# base3-5pin-interface-SDA-SCL-Switch-on-o.net
KiCad netlist of a schematic drawn in EAGLE
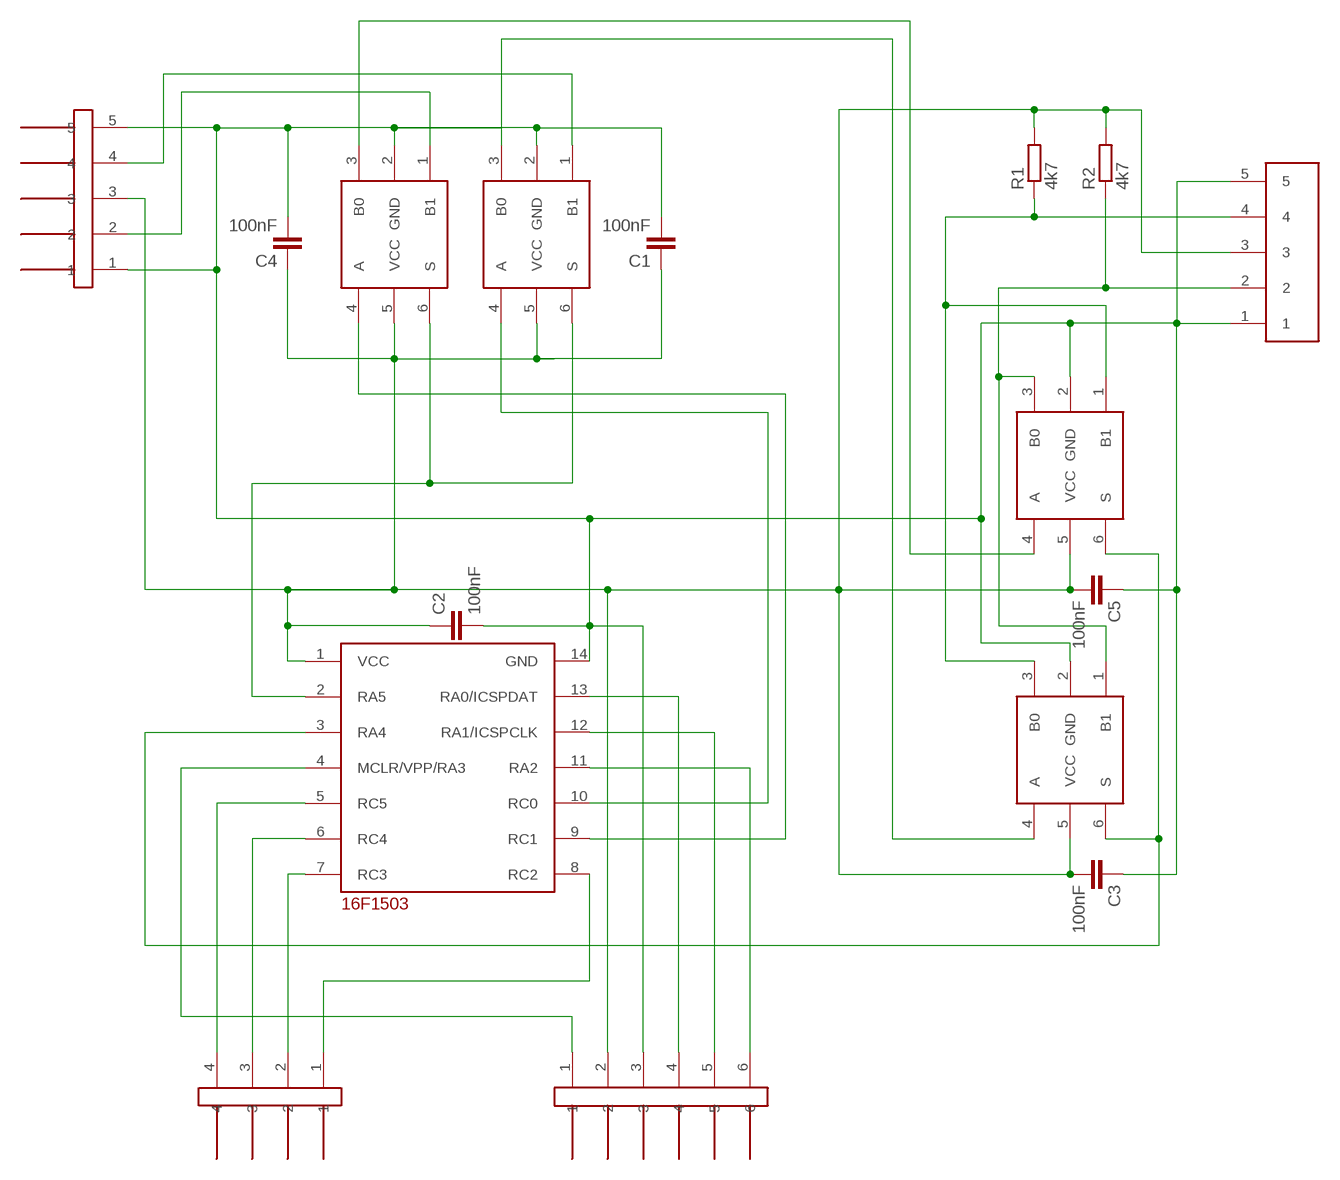
[diagram p0: schematic, sheet 1]

(export (version "E")
  (design (tool "Eeschema 10.0.6"))
  (components
    (comp (ref "C1")
      (value "100nF")
      (footprint "eagle-import:C0603")
      (libsource (lib "eagle-import") (part "C-EUC0603"))
    )
    (comp (ref "C2")
      (value "100nF")
      (footprint "eagle-import:C0603")
      (libsource (lib "eagle-import") (part "C-EUC0603"))
    )
    (comp (ref "C3")
      (value "100nF")
      (footprint "eagle-import:C0603")
      (libsource (lib "eagle-import") (part "C-EUC0603"))
    )
    (comp (ref "C4")
      (value "100nF")
      (footprint "eagle-import:C0603")
      (libsource (lib "eagle-import") (part "C-EUC0603"))
    )
    (comp (ref "C5")
      (value "100nF")
      (footprint "eagle-import:C0603")
      (libsource (lib "eagle-import") (part "C-EUC0603"))
    )
    (comp (ref "R1")
      (value "4k7")
      (footprint "eagle-import:M0805")
      (libsource (lib "eagle-import") (part "R-EU_M0805"))
    )
    (comp (ref "R2")
      (value "4k7")
      (footprint "eagle-import:M0805")
      (libsource (lib "eagle-import") (part "R-EU_M0805"))
    )
    (comp (ref "U$1")
      (value "16F103-TSSOP")
      (footprint "eagle-import:TSSOP14")
      (libsource (lib "eagle-import") (part "16F103-TSSOP"))
    )
    (comp (ref "U$2")
      (value "NC7SB3157P6X")
      (footprint "eagle-import:SC70-6L")
      (libsource (lib "eagle-import") (part "NC7SB3157P6X"))
    )
    (comp (ref "U$3")
      (value "NC7SB3157P6X")
      (footprint "eagle-import:SC70-6L")
      (libsource (lib "eagle-import") (part "NC7SB3157P6X"))
    )
    (comp (ref "U$4")
      (value "JUMPER5M-90")
      (footprint "eagle-import:JUMPER5M-90")
      (libsource (lib "eagle-import") (part "JUMPER5M-90"))
    )
    (comp (ref "U$5")
      (value "JUMPER5F-90")
      (footprint "eagle-import:JUMPER5F-90")
      (libsource (lib "eagle-import") (part "JUMPER5F-90"))
    )
    (comp (ref "U$6")
      (value "NC7SB3157P6X")
      (footprint "eagle-import:SC70-6L")
      (libsource (lib "eagle-import") (part "NC7SB3157P6X"))
    )
    (comp (ref "U$7")
      (value "NC7SB3157P6X")
      (footprint "eagle-import:SC70-6L")
      (libsource (lib "eagle-import") (part "NC7SB3157P6X"))
    )
    (comp (ref "U$8")
      (value "JUMPER6M")
      (footprint "eagle-import:JUMPER6M")
      (libsource (lib "eagle-import") (part "JUMPER6M"))
    )
    (comp (ref "U$9")
      (value "JUMPER4M")
      (footprint "eagle-import:JUMPER4M")
      (libsource (lib "eagle-import") (part "JUMPER4M"))
    )
  )
  (nets
    (net (code "1") (name "Net-(U$1-GND)") (class "Default")
      (node (ref "C1") (pin "2") (pinfunction "2_2") (pintype "passive"))
      (node (ref "C2") (pin "2") (pinfunction "2_2") (pintype "passive"))
      (node (ref "C3") (pin "1") (pinfunction "1_1") (pintype "passive"))
      (node (ref "C4") (pin "2") (pinfunction "2_2") (pintype "passive"))
      (node (ref "C5") (pin "1") (pinfunction "1_1") (pintype "passive"))
      (node (ref "U$1") (pin "14") (pinfunction "GND_14") (pintype "power_in"))
      (node (ref "U$2") (pin "2") (pinfunction "GND_2") (pintype "power_in"))
      (node (ref "U$3") (pin "2") (pinfunction "GND_2") (pintype "power_in"))
      (node (ref "U$4") (pin "1") (pinfunction "1_1") (pintype "bidirectional"))
      (node (ref "U$4") (pin "5") (pinfunction "5_5") (pintype "bidirectional"))
      (node (ref "U$5") (pin "1") (pinfunction "1_1") (pintype "bidirectional"))
      (node (ref "U$5") (pin "5") (pinfunction "5_5") (pintype "bidirectional"))
      (node (ref "U$6") (pin "2") (pinfunction "GND_2") (pintype "power_in"))
      (node (ref "U$7") (pin "2") (pinfunction "GND_2") (pintype "power_in"))
      (node (ref "U$8") (pin "3") (pinfunction "3_3") (pintype "bidirectional"))
    )
    (net (code "2") (name "Net-(U$1-MCLR{slash}VPP{slash}RA3)") (class "Default")
      (node (ref "U$1") (pin "4") (pinfunction "MCLR/VPP/RA3_4") (pintype "bidirectional"))
      (node (ref "U$8") (pin "1") (pinfunction "1_1") (pintype "bidirectional"))
    )
    (net (code "3") (name "Net-(U$1-RA0{slash}ICSPDAT)") (class "Default")
      (node (ref "U$1") (pin "13") (pinfunction "RA0/ICSPDAT_13") (pintype "bidirectional"))
      (node (ref "U$8") (pin "4") (pinfunction "4_4") (pintype "bidirectional"))
    )
    (net (code "4") (name "Net-(U$1-RA1{slash}ICSPCLK)") (class "Default")
      (node (ref "U$1") (pin "12") (pinfunction "RA1/ICSPCLK_12") (pintype "bidirectional"))
      (node (ref "U$8") (pin "5") (pinfunction "5_5") (pintype "bidirectional"))
    )
    (net (code "5") (name "Net-(U$1-RA2)") (class "Default")
      (node (ref "U$1") (pin "11") (pinfunction "RA2_11") (pintype "bidirectional"))
      (node (ref "U$8") (pin "6") (pinfunction "6_6") (pintype "bidirectional"))
    )
    (net (code "6") (name "Net-(U$1-RA4)") (class "Default")
      (node (ref "U$1") (pin "3") (pinfunction "RA4_3") (pintype "bidirectional"))
      (node (ref "U$6") (pin "6") (pinfunction "S_6") (pintype "bidirectional"))
      (node (ref "U$7") (pin "6") (pinfunction "S_6") (pintype "bidirectional"))
    )
    (net (code "7") (name "Net-(U$1-RA5)") (class "Default")
      (node (ref "U$1") (pin "2") (pinfunction "RA5_2") (pintype "bidirectional"))
      (node (ref "U$2") (pin "6") (pinfunction "S_6") (pintype "bidirectional"))
      (node (ref "U$3") (pin "6") (pinfunction "S_6") (pintype "bidirectional"))
    )
    (net (code "8") (name "Net-(U$1-RC0)") (class "Default")
      (node (ref "U$1") (pin "10") (pinfunction "RC0_10") (pintype "bidirectional"))
      (node (ref "U$2") (pin "4") (pinfunction "A_4") (pintype "bidirectional"))
    )
    (net (code "9") (name "Net-(U$1-RC1)") (class "Default")
      (node (ref "U$1") (pin "9") (pinfunction "RC1_9") (pintype "bidirectional"))
      (node (ref "U$3") (pin "4") (pinfunction "A_4") (pintype "bidirectional"))
    )
    (net (code "10") (name "Net-(U$1-RC2)") (class "Default")
      (node (ref "U$1") (pin "8") (pinfunction "RC2_8") (pintype "bidirectional"))
      (node (ref "U$9") (pin "1") (pinfunction "1_1") (pintype "bidirectional"))
    )
    (net (code "11") (name "Net-(U$1-RC3)") (class "Default")
      (node (ref "U$1") (pin "7") (pinfunction "RC3_7") (pintype "bidirectional"))
      (node (ref "U$9") (pin "2") (pinfunction "2_2") (pintype "bidirectional"))
    )
    (net (code "12") (name "Net-(U$1-RC4)") (class "Default")
      (node (ref "U$1") (pin "6") (pinfunction "RC4_6") (pintype "bidirectional"))
      (node (ref "U$9") (pin "3") (pinfunction "3_3") (pintype "bidirectional"))
    )
    (net (code "13") (name "Net-(U$1-RC5)") (class "Default")
      (node (ref "U$1") (pin "5") (pinfunction "RC5_5") (pintype "bidirectional"))
      (node (ref "U$9") (pin "4") (pinfunction "4_4") (pintype "bidirectional"))
    )
    (net (code "14") (name "Net-(U$1-VCC)") (class "Default")
      (node (ref "C1") (pin "1") (pinfunction "1_1") (pintype "passive"))
      (node (ref "C2") (pin "1") (pinfunction "1_1") (pintype "passive"))
      (node (ref "C3") (pin "2") (pinfunction "2_2") (pintype "passive"))
      (node (ref "C4") (pin "1") (pinfunction "1_1") (pintype "passive"))
      (node (ref "C5") (pin "2") (pinfunction "2_2") (pintype "passive"))
      (node (ref "R1") (pin "2") (pinfunction "2_2") (pintype "passive"))
      (node (ref "R2") (pin "2") (pinfunction "2_2") (pintype "passive"))
      (node (ref "U$1") (pin "1") (pinfunction "VCC_1") (pintype "power_in"))
      (node (ref "U$2") (pin "5") (pinfunction "VCC_5") (pintype "power_in"))
      (node (ref "U$3") (pin "5") (pinfunction "VCC_5") (pintype "power_in"))
      (node (ref "U$4") (pin "3") (pinfunction "3_3") (pintype "bidirectional"))
      (node (ref "U$5") (pin "3") (pinfunction "3_3") (pintype "bidirectional"))
      (node (ref "U$6") (pin "5") (pinfunction "VCC_5") (pintype "power_in"))
      (node (ref "U$7") (pin "5") (pinfunction "VCC_5") (pintype "power_in"))
      (node (ref "U$8") (pin "2") (pinfunction "2_2") (pintype "bidirectional"))
    )
    (net (code "15") (name "Net-(U$2-B0)") (class "Default")
      (node (ref "U$2") (pin "3") (pinfunction "B0_3") (pintype "bidirectional"))
      (node (ref "U$7") (pin "4") (pinfunction "A_4") (pintype "bidirectional"))
    )
    (net (code "16") (name "Net-(U$2-B1)") (class "Default")
      (node (ref "U$2") (pin "1") (pinfunction "B1_1") (pintype "bidirectional"))
      (node (ref "U$4") (pin "4") (pinfunction "4_4") (pintype "bidirectional"))
    )
    (net (code "17") (name "Net-(U$3-B0)") (class "Default")
      (node (ref "U$3") (pin "3") (pinfunction "B0_3") (pintype "bidirectional"))
      (node (ref "U$6") (pin "4") (pinfunction "A_4") (pintype "bidirectional"))
    )
    (net (code "18") (name "Net-(U$3-B1)") (class "Default")
      (node (ref "U$3") (pin "1") (pinfunction "B1_1") (pintype "bidirectional"))
      (node (ref "U$4") (pin "2") (pinfunction "2_2") (pintype "bidirectional"))
    )
    (net (code "19") (name "Net-(U$6-B0)") (class "Default")
      (node (ref "R2") (pin "1") (pinfunction "1_1") (pintype "passive"))
      (node (ref "U$5") (pin "2") (pinfunction "2_2") (pintype "bidirectional"))
      (node (ref "U$6") (pin "3") (pinfunction "B0_3") (pintype "bidirectional"))
      (node (ref "U$7") (pin "1") (pinfunction "B1_1") (pintype "bidirectional"))
    )
    (net (code "20") (name "Net-(U$6-B1)") (class "Default")
      (node (ref "R1") (pin "1") (pinfunction "1_1") (pintype "passive"))
      (node (ref "U$5") (pin "4") (pinfunction "4_4") (pintype "bidirectional"))
      (node (ref "U$6") (pin "1") (pinfunction "B1_1") (pintype "bidirectional"))
      (node (ref "U$7") (pin "3") (pinfunction "B0_3") (pintype "bidirectional"))
    )
  )
)
